# RoverWing-cover-V4.net
KiCad netlist of a schematic drawn in EAGLE
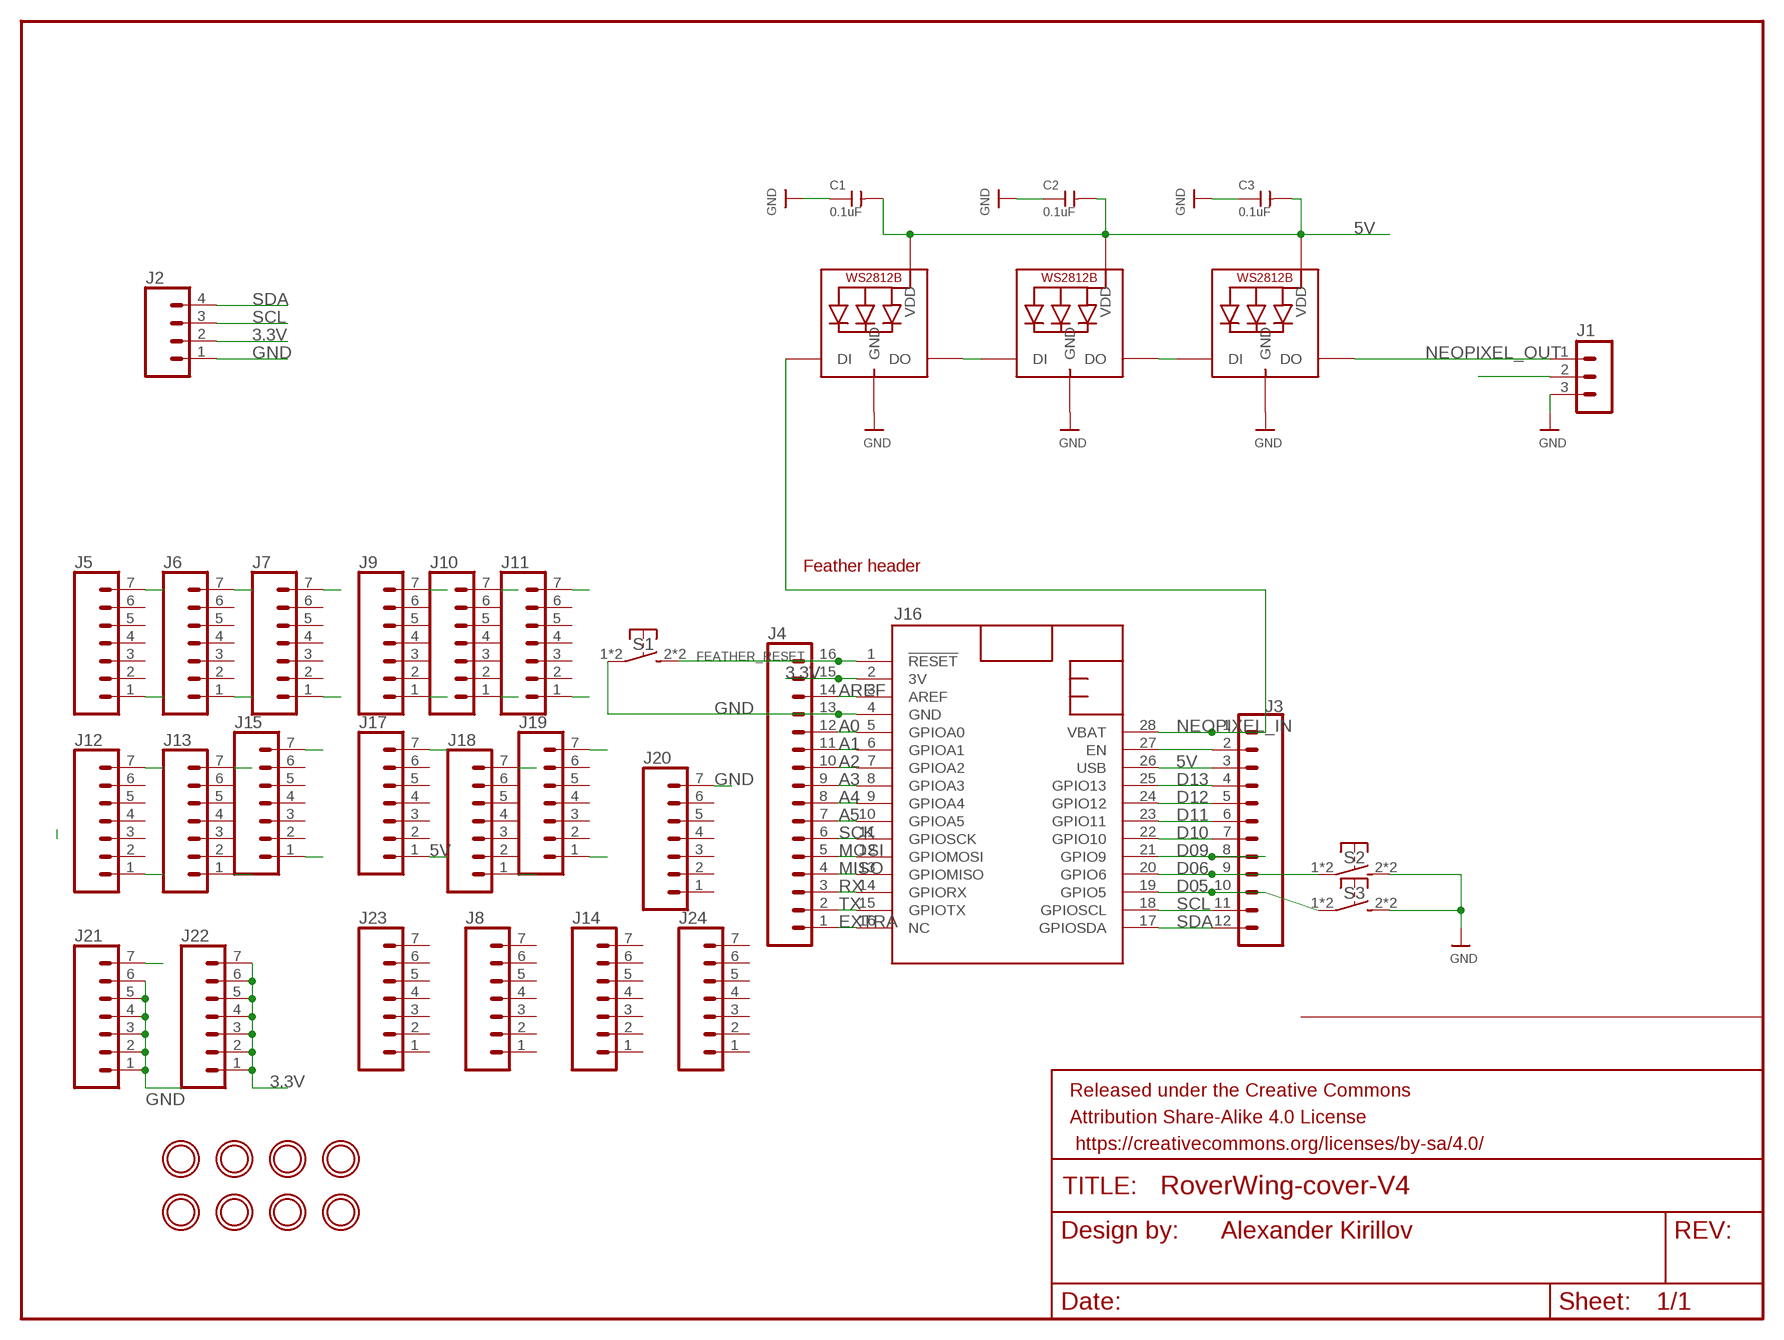
[diagram p0: schematic, sheet 1]

(export (version "E")
  (design (tool "Eeschema 10.0.6"))
  (components
    (comp (ref "C1")
      (value "0.1uF")
      (footprint "eagle-import:C0805")
      (libsource (lib "eagle-import") (part "CAP-CERAMIC-SMD-0805"))
    )
    (comp (ref "C2")
      (value "0.1uF")
      (footprint "eagle-import:C0805")
      (libsource (lib "eagle-import") (part "CAP-CERAMIC-SMD-0805"))
    )
    (comp (ref "C3")
      (value "0.1uF")
      (footprint "eagle-import:C0805")
      (libsource (lib "eagle-import") (part "CAP-CERAMIC-SMD-0805"))
    )
    (comp (ref "FRAME2")
      (value "FRAME-LETTERNO_PACKAGE")
      (footprint "eagle-import:DUMMY")
      (fields (field (name "DESIGNER") "Nobody"))
      (libsource (lib "eagle-import") (part "FRAME-LETTERNO_PACKAGE"))
    )
    (comp (ref "J1")
      (value "HEADER-PH-3P")
      (footprint "eagle-import:B3B-PH-K")
      (fields (field (name "PARTNO") "B3B-PH-K-S(LF)(SN)"))
      (libsource (lib "eagle-import") (part "HEADER-PH-3P"))
    )
    (comp (ref "J2")
      (value "CONN_04")
      (footprint "eagle-import:1X04")
      (libsource (lib "eagle-import") (part "CONN_04"))
    )
    (comp (ref "J3")
      (value "CONN_12NO_SILK")
      (footprint "eagle-import:1X12_NO_SILK")
      (libsource (lib "eagle-import") (part "CONN_12NO_SILK"))
    )
    (comp (ref "J4")
      (value "CONN_161X16_NO_SILK")
      (footprint "eagle-import:1X16_NO_SILK")
      (libsource (lib "eagle-import") (part "CONN_161X16_NO_SILK"))
    )
    (comp (ref "J5")
      (value "CONN_07NO_SILK")
      (footprint "eagle-import:1X07_NO_SILK")
      (libsource (lib "eagle-import") (part "CONN_07NO_SILK"))
    )
    (comp (ref "J6")
      (value "CONN_07NO_SILK")
      (footprint "eagle-import:1X07_NO_SILK")
      (libsource (lib "eagle-import") (part "CONN_07NO_SILK"))
    )
    (comp (ref "J7")
      (value "CONN_07NO_SILK")
      (footprint "eagle-import:1X07_NO_SILK")
      (libsource (lib "eagle-import") (part "CONN_07NO_SILK"))
    )
    (comp (ref "J8")
      (value "CONN_07NO_SILK")
      (footprint "eagle-import:1X07_NO_SILK")
      (libsource (lib "eagle-import") (part "CONN_07NO_SILK"))
    )
    (comp (ref "J9")
      (value "CONN_07NO_SILK")
      (footprint "eagle-import:1X07_NO_SILK")
      (libsource (lib "eagle-import") (part "CONN_07NO_SILK"))
    )
    (comp (ref "J10")
      (value "CONN_07NO_SILK")
      (footprint "eagle-import:1X07_NO_SILK")
      (libsource (lib "eagle-import") (part "CONN_07NO_SILK"))
    )
    (comp (ref "J11")
      (value "CONN_07NO_SILK")
      (footprint "eagle-import:1X07_NO_SILK")
      (libsource (lib "eagle-import") (part "CONN_07NO_SILK"))
    )
    (comp (ref "J12")
      (value "CONN_07NO_SILK")
      (footprint "eagle-import:1X07_NO_SILK")
      (libsource (lib "eagle-import") (part "CONN_07NO_SILK"))
    )
    (comp (ref "J13")
      (value "CONN_07NO_SILK")
      (footprint "eagle-import:1X07_NO_SILK")
      (libsource (lib "eagle-import") (part "CONN_07NO_SILK"))
    )
    (comp (ref "J14")
      (value "CONN_07NO_SILK")
      (footprint "eagle-import:1X07_NO_SILK")
      (libsource (lib "eagle-import") (part "CONN_07NO_SILK"))
    )
    (comp (ref "J15")
      (value "CONN_07NO_SILK")
      (footprint "eagle-import:1X07_NO_SILK")
      (libsource (lib "eagle-import") (part "CONN_07NO_SILK"))
    )
    (comp (ref "J16")
      (value "FEATHERWING_NODIM")
      (footprint "eagle-import:FEATHERWING_DIM")
      (libsource (lib "eagle-import") (part "FEATHERWING_NODIM"))
    )
    (comp (ref "J17")
      (value "CONN_07NO_SILK")
      (footprint "eagle-import:1X07_NO_SILK")
      (libsource (lib "eagle-import") (part "CONN_07NO_SILK"))
    )
    (comp (ref "J18")
      (value "CONN_07NO_SILK")
      (footprint "eagle-import:1X07_NO_SILK")
      (libsource (lib "eagle-import") (part "CONN_07NO_SILK"))
    )
    (comp (ref "J19")
      (value "CONN_07NO_SILK")
      (footprint "eagle-import:1X07_NO_SILK")
      (libsource (lib "eagle-import") (part "CONN_07NO_SILK"))
    )
    (comp (ref "J20")
      (value "CONN_07NO_SILK")
      (footprint "eagle-import:1X07_NO_SILK")
      (libsource (lib "eagle-import") (part "CONN_07NO_SILK"))
    )
    (comp (ref "J21")
      (value "CONN_07NO_SILK")
      (footprint "eagle-import:1X07_NO_SILK")
      (libsource (lib "eagle-import") (part "CONN_07NO_SILK"))
    )
    (comp (ref "J22")
      (value "CONN_07NO_SILK")
      (footprint "eagle-import:1X07_NO_SILK")
      (libsource (lib "eagle-import") (part "CONN_07NO_SILK"))
    )
    (comp (ref "J23")
      (value "CONN_07NO_SILK")
      (footprint "eagle-import:1X07_NO_SILK")
      (libsource (lib "eagle-import") (part "CONN_07NO_SILK"))
    )
    (comp (ref "J24")
      (value "CONN_07NO_SILK")
      (footprint "eagle-import:1X07_NO_SILK")
      (libsource (lib "eagle-import") (part "CONN_07NO_SILK"))
    )
    (comp (ref "LED1")
      (value "WS2812B5050")
      (footprint "eagle-import:WS2812B")
      (libsource (lib "eagle-import") (part "WS2812B5050"))
    )
    (comp (ref "LED2")
      (value "WS2812B5050")
      (footprint "eagle-import:WS2812B")
      (libsource (lib "eagle-import") (part "WS2812B5050"))
    )
    (comp (ref "LED3")
      (value "WS2812B5050")
      (footprint "eagle-import:WS2812B")
      (libsource (lib "eagle-import") (part "WS2812B5050"))
    )
    (comp (ref "S1")
      (value "SW-TACTILE-4.5X4.5_SMD")
      (footprint "eagle-import:TL3305")
      (libsource (lib "eagle-import") (part "SW-TACTILE-4.5X4.5_SMD"))
    )
    (comp (ref "S2")
      (value "SW-TACTILE-4.5X4.5_SMD")
      (footprint "eagle-import:TL3305")
      (libsource (lib "eagle-import") (part "SW-TACTILE-4.5X4.5_SMD"))
    )
    (comp (ref "S3")
      (value "SW-TACTILE-4.5X4.5_SMD")
      (footprint "eagle-import:TL3305")
      (libsource (lib "eagle-import") (part "SW-TACTILE-4.5X4.5_SMD"))
    )
    (comp (ref "U$3")
      (value "MOUNTINGHOLE3.0_NPH")
      (footprint "eagle-import:MOUNTINGHOLE_3.0_NPH")
      (libsource (lib "eagle-import") (part "MOUNTINGHOLE3.0_NPH"))
    )
    (comp (ref "U$4")
      (value "MOUNTINGHOLE3.0_NPH")
      (footprint "eagle-import:MOUNTINGHOLE_3.0_NPH")
      (libsource (lib "eagle-import") (part "MOUNTINGHOLE3.0_NPH"))
    )
    (comp (ref "U$14")
      (value "MOUNTINGHOLE3.0_NPH")
      (footprint "eagle-import:MOUNTINGHOLE_3.0_NPH")
      (libsource (lib "eagle-import") (part "MOUNTINGHOLE3.0_NPH"))
    )
    (comp (ref "U$15")
      (value "MOUNTINGHOLE3.0_NPH")
      (footprint "eagle-import:MOUNTINGHOLE_3.0_NPH")
      (libsource (lib "eagle-import") (part "MOUNTINGHOLE3.0_NPH"))
    )
    (comp (ref "U$24")
      (value "MOUNTINGHOLE3.0_NPH")
      (footprint "eagle-import:MOUNTINGHOLE_3.0_NPH")
      (libsource (lib "eagle-import") (part "MOUNTINGHOLE3.0_NPH"))
    )
    (comp (ref "U$25")
      (value "MOUNTINGHOLE3.0_NPH")
      (footprint "eagle-import:MOUNTINGHOLE_3.0_NPH")
      (libsource (lib "eagle-import") (part "MOUNTINGHOLE3.0_NPH"))
    )
    (comp (ref "U$26")
      (value "MOUNTINGHOLE3.0_NPH")
      (footprint "eagle-import:MOUNTINGHOLE_3.0_NPH")
      (libsource (lib "eagle-import") (part "MOUNTINGHOLE3.0_NPH"))
    )
    (comp (ref "U$27")
      (value "MOUNTINGHOLE3.0_NPH")
      (footprint "eagle-import:MOUNTINGHOLE_3.0_NPH")
      (libsource (lib "eagle-import") (part "MOUNTINGHOLE3.0_NPH"))
    )
  )
  (nets
    (net (code "1") (name "/3.3V") (class "Default")
      (node (ref "J16") (pin "2") (pinfunction "3V_2") (pintype "power_in"))
      (node (ref "J2") (pin "2") (pinfunction "2_2") (pintype "passive"))
      (node (ref "J22") (pin "1") (pinfunction "1_1") (pintype "passive"))
      (node (ref "J22") (pin "2") (pinfunction "2_2") (pintype "passive"))
      (node (ref "J22") (pin "3") (pinfunction "3_3") (pintype "passive"))
      (node (ref "J22") (pin "4") (pinfunction "4_4") (pintype "passive"))
      (node (ref "J22") (pin "5") (pinfunction "5_5") (pintype "passive"))
      (node (ref "J22") (pin "6") (pinfunction "6_6") (pintype "passive"))
      (node (ref "J22") (pin "7") (pinfunction "7_7") (pintype "passive"))
      (node (ref "J4") (pin "15") (pinfunction "15_15") (pintype "passive"))
    )
    (net (code "2") (name "/5V") (class "Default")
      (node (ref "C1") (pin "2") (pinfunction "2_2") (pintype "passive"))
      (node (ref "C2") (pin "2") (pinfunction "2_2") (pintype "passive"))
      (node (ref "C3") (pin "2") (pinfunction "2_2") (pintype "passive"))
      (node (ref "J1") (pin "2") (pinfunction "2_2") (pintype "passive"))
      (node (ref "J16") (pin "26") (pinfunction "USB_26") (pintype "power_in"))
      (node (ref "J17") (pin "1") (pinfunction "1_1") (pintype "passive"))
      (node (ref "J3") (pin "3") (pinfunction "3_3") (pintype "passive"))
      (node (ref "LED1") (pin "1-VDD") (pinfunction "VDD_1-VDD") (pintype "power_in"))
      (node (ref "LED2") (pin "1-VDD") (pinfunction "VDD_1-VDD") (pintype "power_in"))
      (node (ref "LED3") (pin "1-VDD") (pinfunction "VDD_1-VDD") (pintype "power_in"))
    )
    (net (code "3") (name "/A0") (class "Default")
      (node (ref "J16") (pin "5") (pinfunction "GPIOA0_5") (pintype "bidirectional"))
      (node (ref "J19") (pin "7") (pinfunction "7_7") (pintype "passive"))
      (node (ref "J4") (pin "12") (pinfunction "12_12") (pintype "passive"))
    )
    (net (code "4") (name "/A1") (class "Default")
      (node (ref "J16") (pin "6") (pinfunction "GPIOA1_6") (pintype "bidirectional"))
      (node (ref "J18") (pin "7") (pinfunction "7_7") (pintype "passive"))
      (node (ref "J4") (pin "11") (pinfunction "11_11") (pintype "passive"))
    )
    (net (code "5") (name "/A2") (class "Default")
      (node (ref "J16") (pin "7") (pinfunction "GPIOA2_7") (pintype "bidirectional"))
      (node (ref "J17") (pin "7") (pinfunction "7_7") (pintype "passive"))
      (node (ref "J4") (pin "10") (pinfunction "10_10") (pintype "passive"))
    )
    (net (code "6") (name "/A3") (class "Default")
      (node (ref "J15") (pin "7") (pinfunction "7_7") (pintype "passive"))
      (node (ref "J16") (pin "8") (pinfunction "GPIOA3_8") (pintype "bidirectional"))
      (node (ref "J4") (pin "9") (pinfunction "9_9") (pintype "passive"))
    )
    (net (code "7") (name "/A4") (class "Default")
      (node (ref "J13") (pin "7") (pinfunction "7_7") (pintype "passive"))
      (node (ref "J16") (pin "9") (pinfunction "GPIOA4_9") (pintype "bidirectional"))
      (node (ref "J4") (pin "8") (pinfunction "8_8") (pintype "passive"))
    )
    (net (code "8") (name "/A5") (class "Default")
      (node (ref "J12") (pin "7") (pinfunction "7_7") (pintype "passive"))
      (node (ref "J16") (pin "10") (pinfunction "GPIOA5_10") (pintype "bidirectional"))
      (node (ref "J4") (pin "7") (pinfunction "7_7") (pintype "passive"))
    )
    (net (code "9") (name "/AREF") (class "Default")
      (node (ref "J16") (pin "3") (pinfunction "AREF_3") (pintype "passive"))
      (node (ref "J21") (pin "7") (pinfunction "7_7") (pintype "passive"))
      (node (ref "J4") (pin "14") (pinfunction "14_14") (pintype "passive"))
    )
    (net (code "10") (name "/D05") (class "Default")
      (node (ref "J16") (pin "19") (pinfunction "GPIO5_19") (pintype "bidirectional"))
      (node (ref "J3") (pin "10") (pinfunction "10_10") (pintype "passive"))
      (node (ref "J7") (pin "1") (pinfunction "1_1") (pintype "passive"))
      (node (ref "S3") (pin "1") (pinfunction "P1_1") (pintype "passive"))
      (node (ref "S3") (pin "4") (pinfunction "P1_4") (pintype "passive"))
    )
    (net (code "11") (name "/D06") (class "Default")
      (node (ref "J16") (pin "20") (pinfunction "GPIO6_20") (pintype "bidirectional"))
      (node (ref "J3") (pin "9") (pinfunction "9_9") (pintype "passive"))
      (node (ref "J9") (pin "1") (pinfunction "1_1") (pintype "passive"))
      (node (ref "S2") (pin "1") (pinfunction "P1_1") (pintype "passive"))
      (node (ref "S2") (pin "4") (pinfunction "P1_4") (pintype "passive"))
    )
    (net (code "12") (name "/D09") (class "Default")
      (node (ref "J10") (pin "1") (pinfunction "1_1") (pintype "passive"))
      (node (ref "J16") (pin "21") (pinfunction "GPIO9_21") (pintype "bidirectional"))
      (node (ref "J3") (pin "8") (pinfunction "8_8") (pintype "passive"))
    )
    (net (code "13") (name "/D10") (class "Default")
      (node (ref "J11") (pin "1") (pinfunction "1_1") (pintype "passive"))
      (node (ref "J16") (pin "22") (pinfunction "GPIO10_22") (pintype "bidirectional"))
      (node (ref "J3") (pin "7") (pinfunction "7_7") (pintype "passive"))
    )
    (net (code "14") (name "/D11") (class "Default")
      (node (ref "J12") (pin "1") (pinfunction "1_1") (pintype "passive"))
      (node (ref "J16") (pin "23") (pinfunction "GPIO11_23") (pintype "bidirectional"))
      (node (ref "J3") (pin "6") (pinfunction "6_6") (pintype "passive"))
    )
    (net (code "15") (name "/D12") (class "Default")
      (node (ref "J13") (pin "1") (pinfunction "1_1") (pintype "passive"))
      (node (ref "J16") (pin "24") (pinfunction "GPIO12_24") (pintype "bidirectional"))
      (node (ref "J3") (pin "5") (pinfunction "5_5") (pintype "passive"))
    )
    (net (code "16") (name "/D13") (class "Default")
      (node (ref "J15") (pin "1") (pinfunction "1_1") (pintype "passive"))
      (node (ref "J16") (pin "25") (pinfunction "GPIO13_25") (pintype "bidirectional"))
      (node (ref "J3") (pin "4") (pinfunction "4_4") (pintype "passive"))
    )
    (net (code "17") (name "/EXTRA") (class "Default")
      (node (ref "J16") (pin "16") (pinfunction "NC_16") (pintype "passive"))
      (node (ref "J4") (pin "1") (pinfunction "1_1") (pintype "passive"))
      (node (ref "J5") (pin "7") (pinfunction "7_7") (pintype "passive"))
    )
    (net (code "18") (name "/FEATHER_RESET") (class "Default")
      (node (ref "J16") (pin "1") (pinfunction "~{RESET}_1") (pintype "input"))
      (node (ref "J4") (pin "16") (pinfunction "16_16") (pintype "passive"))
      (node (ref "S1") (pin "2") (pinfunction "S1_2") (pintype "passive"))
      (node (ref "S1") (pin "3") (pinfunction "S1_3") (pintype "passive"))
    )
    (net (code "19") (name "/MISO") (class "Default")
      (node (ref "J16") (pin "13") (pinfunction "GPIOMISO_13") (pintype "bidirectional"))
      (node (ref "J4") (pin "4") (pinfunction "4_4") (pintype "passive"))
      (node (ref "J9") (pin "7") (pinfunction "7_7") (pintype "passive"))
    )
    (net (code "20") (name "/MOSI") (class "Default")
      (node (ref "J10") (pin "7") (pinfunction "7_7") (pintype "passive"))
      (node (ref "J16") (pin "12") (pinfunction "GPIOMOSI_12") (pintype "bidirectional"))
      (node (ref "J4") (pin "5") (pinfunction "5_5") (pintype "passive"))
    )
    (net (code "21") (name "/N$37") (class "Default")
      (node (ref "J16") (pin "27") (pinfunction "EN_27") (pintype "passive"))
      (node (ref "J18") (pin "1") (pinfunction "1_1") (pintype "passive"))
      (node (ref "J3") (pin "2") (pinfunction "2_2") (pintype "passive"))
    )
    (net (code "22") (name "/NEOPIXEL_IN") (class "Default")
      (node (ref "J16") (pin "28") (pinfunction "VBAT_28") (pintype "power_in"))
      (node (ref "J3") (pin "1") (pinfunction "1_1") (pintype "passive"))
      (node (ref "LED1") (pin "4-DIN") (pinfunction "DI_4-DIN") (pintype "input"))
    )
    (net (code "23") (name "/NEOPIXEL_OUT") (class "Default")
      (node (ref "J1") (pin "1") (pinfunction "1_1") (pintype "passive"))
      (node (ref "LED3") (pin "2-DOUT") (pinfunction "DO_2-DOUT") (pintype "output"))
    )
    (net (code "24") (name "/RX") (class "Default")
      (node (ref "J16") (pin "14") (pinfunction "GPIORX_14") (pintype "bidirectional"))
      (node (ref "J4") (pin "3") (pinfunction "3_3") (pintype "passive"))
      (node (ref "J7") (pin "7") (pinfunction "7_7") (pintype "passive"))
    )
    (net (code "25") (name "/SCK") (class "Default")
      (node (ref "J11") (pin "7") (pinfunction "7_7") (pintype "passive"))
      (node (ref "J16") (pin "11") (pinfunction "GPIOSCK_11") (pintype "bidirectional"))
      (node (ref "J4") (pin "6") (pinfunction "6_6") (pintype "passive"))
    )
    (net (code "26") (name "/SCL") (class "Default")
      (node (ref "J16") (pin "18") (pinfunction "GPIOSCL_18") (pintype "bidirectional"))
      (node (ref "J2") (pin "3") (pinfunction "3_3") (pintype "passive"))
      (node (ref "J3") (pin "11") (pinfunction "11_11") (pintype "passive"))
      (node (ref "J6") (pin "1") (pinfunction "1_1") (pintype "passive"))
    )
    (net (code "27") (name "/SDA") (class "Default")
      (node (ref "J16") (pin "17") (pinfunction "GPIOSDA_17") (pintype "bidirectional"))
      (node (ref "J2") (pin "4") (pinfunction "4_4") (pintype "passive"))
      (node (ref "J3") (pin "12") (pinfunction "12_12") (pintype "passive"))
      (node (ref "J5") (pin "1") (pinfunction "1_1") (pintype "passive"))
    )
    (net (code "28") (name "/TX") (class "Default")
      (node (ref "J16") (pin "15") (pinfunction "GPIOTX_15") (pintype "bidirectional"))
      (node (ref "J4") (pin "2") (pinfunction "2_2") (pintype "passive"))
      (node (ref "J6") (pin "7") (pinfunction "7_7") (pintype "passive"))
    )
    (net (code "29") (name "GND") (class "Default")
      (node (ref "C1") (pin "1") (pinfunction "1_1") (pintype "passive"))
      (node (ref "C2") (pin "1") (pinfunction "1_1") (pintype "passive"))
      (node (ref "C3") (pin "1") (pinfunction "1_1") (pintype "passive"))
      (node (ref "J1") (pin "3") (pinfunction "3_3") (pintype "passive"))
      (node (ref "J16") (pin "4") (pinfunction "GND_4") (pintype "power_in"))
      (node (ref "J2") (pin "1") (pinfunction "1_1") (pintype "passive"))
      (node (ref "J20") (pin "7") (pinfunction "7_7") (pintype "passive"))
      (node (ref "J21") (pin "1") (pinfunction "1_1") (pintype "passive"))
      (node (ref "J21") (pin "2") (pinfunction "2_2") (pintype "passive"))
      (node (ref "J21") (pin "3") (pinfunction "3_3") (pintype "passive"))
      (node (ref "J21") (pin "4") (pinfunction "4_4") (pintype "passive"))
      (node (ref "J21") (pin "5") (pinfunction "5_5") (pintype "passive"))
      (node (ref "J21") (pin "6") (pinfunction "6_6") (pintype "passive"))
      (node (ref "J4") (pin "13") (pinfunction "13_13") (pintype "passive"))
      (node (ref "LED1") (pin "3-GND") (pinfunction "GND_3-GND") (pintype "power_in"))
      (node (ref "LED2") (pin "3-GND") (pinfunction "GND_3-GND") (pintype "power_in"))
      (node (ref "LED3") (pin "3-GND") (pinfunction "GND_3-GND") (pintype "power_in"))
      (node (ref "S1") (pin "1") (pinfunction "P1_1") (pintype "passive"))
      (node (ref "S1") (pin "4") (pinfunction "P1_4") (pintype "passive"))
      (node (ref "S2") (pin "2") (pinfunction "S1_2") (pintype "passive"))
      (node (ref "S2") (pin "3") (pinfunction "S1_3") (pintype "passive"))
      (node (ref "S3") (pin "2") (pinfunction "S1_2") (pintype "passive"))
      (node (ref "S3") (pin "3") (pinfunction "S1_3") (pintype "passive"))
    )
    (net (code "30") (name "Net-(LED1-DO)") (class "Default")
      (node (ref "LED1") (pin "2-DOUT") (pinfunction "DO_2-DOUT") (pintype "output"))
      (node (ref "LED2") (pin "4-DIN") (pinfunction "DI_4-DIN") (pintype "input"))
    )
    (net (code "31") (name "Net-(LED2-DO)") (class "Default")
      (node (ref "LED2") (pin "2-DOUT") (pinfunction "DO_2-DOUT") (pintype "output"))
      (node (ref "LED3") (pin "4-DIN") (pinfunction "DI_4-DIN") (pintype "input"))
    )
    (net (code "32") (name "unconnected-(J5-Pad2)") (class "Default")
      (node (ref "J5") (pin "2") (pinfunction "2_2") (pintype "passive"))
    )
    (net (code "33") (name "unconnected-(J5-Pad3)") (class "Default")
      (node (ref "J5") (pin "3") (pinfunction "3_3") (pintype "passive"))
    )
    (net (code "34") (name "unconnected-(J5-Pad4)") (class "Default")
      (node (ref "J5") (pin "4") (pinfunction "4_4") (pintype "passive"))
    )
    (net (code "35") (name "unconnected-(J5-Pad5)") (class "Default")
      (node (ref "J5") (pin "5") (pinfunction "5_5") (pintype "passive"))
    )
    (net (code "36") (name "unconnected-(J5-Pad6)") (class "Default")
      (node (ref "J5") (pin "6") (pinfunction "6_6") (pintype "passive"))
    )
    (net (code "37") (name "unconnected-(J6-Pad2)") (class "Default")
      (node (ref "J6") (pin "2") (pinfunction "2_2") (pintype "passive"))
    )
    (net (code "38") (name "unconnected-(J6-Pad3)") (class "Default")
      (node (ref "J6") (pin "3") (pinfunction "3_3") (pintype "passive"))
    )
    (net (code "39") (name "unconnected-(J6-Pad4)") (class "Default")
      (node (ref "J6") (pin "4") (pinfunction "4_4") (pintype "passive"))
    )
    (net (code "40") (name "unconnected-(J6-Pad5)") (class "Default")
      (node (ref "J6") (pin "5") (pinfunction "5_5") (pintype "passive"))
    )
    (net (code "41") (name "unconnected-(J6-Pad6)") (class "Default")
      (node (ref "J6") (pin "6") (pinfunction "6_6") (pintype "passive"))
    )
    (net (code "42") (name "unconnected-(J7-Pad2)") (class "Default")
      (node (ref "J7") (pin "2") (pinfunction "2_2") (pintype "passive"))
    )
    (net (code "43") (name "unconnected-(J7-Pad3)") (class "Default")
      (node (ref "J7") (pin "3") (pinfunction "3_3") (pintype "passive"))
    )
    (net (code "44") (name "unconnected-(J7-Pad4)") (class "Default")
      (node (ref "J7") (pin "4") (pinfunction "4_4") (pintype "passive"))
    )
    (net (code "45") (name "unconnected-(J7-Pad5)") (class "Default")
      (node (ref "J7") (pin "5") (pinfunction "5_5") (pintype "passive"))
    )
    (net (code "46") (name "unconnected-(J7-Pad6)") (class "Default")
      (node (ref "J7") (pin "6") (pinfunction "6_6") (pintype "passive"))
    )
    (net (code "47") (name "unconnected-(J8-Pad1)") (class "Default")
      (node (ref "J8") (pin "1") (pinfunction "1_1") (pintype "passive"))
    )
    (net (code "48") (name "unconnected-(J8-Pad2)") (class "Default")
      (node (ref "J8") (pin "2") (pinfunction "2_2") (pintype "passive"))
    )
    (net (code "49") (name "unconnected-(J8-Pad3)") (class "Default")
      (node (ref "J8") (pin "3") (pinfunction "3_3") (pintype "passive"))
    )
    (net (code "50") (name "unconnected-(J8-Pad4)") (class "Default")
      (node (ref "J8") (pin "4") (pinfunction "4_4") (pintype "passive"))
    )
    (net (code "51") (name "unconnected-(J8-Pad5)") (class "Default")
      (node (ref "J8") (pin "5") (pinfunction "5_5") (pintype "passive"))
    )
    (net (code "52") (name "unconnected-(J8-Pad6)") (class "Default")
      (node (ref "J8") (pin "6") (pinfunction "6_6") (pintype "passive"))
    )
    (net (code "53") (name "unconnected-(J8-Pad7)") (class "Default")
      (node (ref "J8") (pin "7") (pinfunction "7_7") (pintype "passive"))
    )
    (net (code "54") (name "unconnected-(J9-Pad2)") (class "Default")
      (node (ref "J9") (pin "2") (pinfunction "2_2") (pintype "passive"))
    )
    (net (code "55") (name "unconnected-(J9-Pad3)") (class "Default")
      (node (ref "J9") (pin "3") (pinfunction "3_3") (pintype "passive"))
    )
    (net (code "56") (name "unconnected-(J9-Pad4)") (class "Default")
      (node (ref "J9") (pin "4") (pinfunction "4_4") (pintype "passive"))
    )
    (net (code "57") (name "unconnected-(J9-Pad5)") (class "Default")
      (node (ref "J9") (pin "5") (pinfunction "5_5") (pintype "passive"))
    )
    (net (code "58") (name "unconnected-(J9-Pad6)") (class "Default")
      (node (ref "J9") (pin "6") (pinfunction "6_6") (pintype "passive"))
    )
    (net (code "59") (name "unconnected-(J10-Pad2)") (class "Default")
      (node (ref "J10") (pin "2") (pinfunction "2_2") (pintype "passive"))
    )
    (net (code "60") (name "unconnected-(J10-Pad3)") (class "Default")
      (node (ref "J10") (pin "3") (pinfunction "3_3") (pintype "passive"))
    )
    (net (code "61") (name "unconnected-(J10-Pad4)") (class "Default")
      (node (ref "J10") (pin "4") (pinfunction "4_4") (pintype "passive"))
    )
    (net (code "62") (name "unconnected-(J10-Pad5)") (class "Default")
      (node (ref "J10") (pin "5") (pinfunction "5_5") (pintype "passive"))
    )
    (net (code "63") (name "unconnected-(J10-Pad6)") (class "Default")
      (node (ref "J10") (pin "6") (pinfunction "6_6") (pintype "passive"))
    )
    (net (code "64") (name "unconnected-(J11-Pad2)") (class "Default")
      (node (ref "J11") (pin "2") (pinfunction "2_2") (pintype "passive"))
    )
    (net (code "65") (name "unconnected-(J11-Pad3)") (class "Default")
      (node (ref "J11") (pin "3") (pinfunction "3_3") (pintype "passive"))
    )
    (net (code "66") (name "unconnected-(J11-Pad4)") (class "Default")
      (node (ref "J11") (pin "4") (pinfunction "4_4") (pintype "passive"))
    )
    (net (code "67") (name "unconnected-(J11-Pad5)") (class "Default")
      (node (ref "J11") (pin "5") (pinfunction "5_5") (pintype "passive"))
    )
    (net (code "68") (name "unconnected-(J11-Pad6)") (class "Default")
      (node (ref "J11") (pin "6") (pinfunction "6_6") (pintype "passive"))
    )
    (net (code "69") (name "unconnected-(J12-Pad2)") (class "Default")
      (node (ref "J12") (pin "2") (pinfunction "2_2") (pintype "passive"))
    )
    (net (code "70") (name "unconnected-(J12-Pad3)") (class "Default")
      (node (ref "J12") (pin "3") (pinfunction "3_3") (pintype "passive"))
    )
    (net (code "71") (name "unconnected-(J12-Pad4)") (class "Default")
      (node (ref "J12") (pin "4") (pinfunction "4_4") (pintype "passive"))
    )
    (net (code "72") (name "unconnected-(J12-Pad5)") (class "Default")
      (node (ref "J12") (pin "5") (pinfunction "5_5") (pintype "passive"))
    )
    (net (code "73") (name "unconnected-(J12-Pad6)") (class "Default")
      (node (ref "J12") (pin "6") (pinfunction "6_6") (pintype "passive"))
    )
    (net (code "74") (name "unconnected-(J13-Pad2)") (class "Default")
      (node (ref "J13") (pin "2") (pinfunction "2_2") (pintype "passive"))
    )
    (net (code "75") (name "unconnected-(J13-Pad3)") (class "Default")
      (node (ref "J13") (pin "3") (pinfunction "3_3") (pintype "passive"))
    )
    (net (code "76") (name "unconnected-(J13-Pad4)") (class "Default")
      (node (ref "J13") (pin "4") (pinfunction "4_4") (pintype "passive"))
    )
    (net (code "77") (name "unconnected-(J13-Pad5)") (class "Default")
      (node (ref "J13") (pin "5") (pinfunction "5_5") (pintype "passive"))
    )
    (net (code "78") (name "unconnected-(J13-Pad6)") (class "Default")
      (node (ref "J13") (pin "6") (pinfunction "6_6") (pintype "passive"))
    )
    (net (code "79") (name "unconnected-(J14-Pad1)") (class "Default")
      (node (ref "J14") (pin "1") (pinfunction "1_1") (pintype "passive"))
    )
    (net (code "80") (name "unconnected-(J14-Pad2)") (class "Default")
      (node (ref "J14") (pin "2") (pinfunction "2_2") (pintype "passive"))
    )
    (net (code "81") (name "unconnected-(J14-Pad3)") (class "Default")
      (node (ref "J14") (pin "3") (pinfunction "3_3") (pintype "passive"))
    )
    (net (code "82") (name "unconnected-(J14-Pad4)") (class "Default")
      (node (ref "J14") (pin "4") (pinfunction "4_4") (pintype "passive"))
    )
    (net (code "83") (name "unconnected-(J14-Pad5)") (class "Default")
      (node (ref "J14") (pin "5") (pinfunction "5_5") (pintype "passive"))
    )
    (net (code "84") (name "unconnected-(J14-Pad6)") (class "Default")
      (node (ref "J14") (pin "6") (pinfunction "6_6") (pintype "passive"))
    )
    (net (code "85") (name "unconnected-(J14-Pad7)") (class "Default")
      (node (ref "J14") (pin "7") (pinfunction "7_7") (pintype "passive"))
    )
    (net (code "86") (name "unconnected-(J15-Pad2)") (class "Default")
      (node (ref "J15") (pin "2") (pinfunction "2_2") (pintype "passive"))
    )
    (net (code "87") (name "unconnected-(J15-Pad3)") (class "Default")
      (node (ref "J15") (pin "3") (pinfunction "3_3") (pintype "passive"))
    )
    (net (code "88") (name "unconnected-(J15-Pad4)") (class "Default")
      (node (ref "J15") (pin "4") (pinfunction "4_4") (pintype "passive"))
    )
    (net (code "89") (name "unconnected-(J15-Pad5)") (class "Default")
      (node (ref "J15") (pin "5") (pinfunction "5_5") (pintype "passive"))
    )
    (net (code "90") (name "unconnected-(J15-Pad6)") (class "Default")
      (node (ref "J15") (pin "6") (pinfunction "6_6") (pintype "passive"))
    )
    (net (code "91") (name "unconnected-(J17-Pad2)") (class "Default")
      (node (ref "J17") (pin "2") (pinfunction "2_2") (pintype "passive"))
    )
    (net (code "92") (name "unconnected-(J17-Pad3)") (class "Default")
      (node (ref "J17") (pin "3") (pinfunction "3_3") (pintype "passive"))
    )
    (net (code "93") (name "unconnected-(J17-Pad4)") (class "Default")
      (node (ref "J17") (pin "4") (pinfunction "4_4") (pintype "passive"))
    )
    (net (code "94") (name "unconnected-(J17-Pad5)") (class "Default")
      (node (ref "J17") (pin "5") (pinfunction "5_5") (pintype "passive"))
    )
    (net (code "95") (name "unconnected-(J17-Pad6)") (class "Default")
      (node (ref "J17") (pin "6") (pinfunction "6_6") (pintype "passive"))
    )
    (net (code "96") (name "unconnected-(J18-Pad2)") (class "Default")
      (node (ref "J18") (pin "2") (pinfunction "2_2") (pintype "passive"))
    )
    (net (code "97") (name "unconnected-(J18-Pad3)") (class "Default")
      (node (ref "J18") (pin "3") (pinfunction "3_3") (pintype "passive"))
    )
    (net (code "98") (name "unconnected-(J18-Pad4)") (class "Default")
      (node (ref "J18") (pin "4") (pinfunction "4_4") (pintype "passive"))
    )
    (net (code "99") (name "unconnected-(J18-Pad5)") (class "Default")
      (node (ref "J18") (pin "5") (pinfunction "5_5") (pintype "passive"))
    )
    (net (code "100") (name "unconnected-(J18-Pad6)") (class "Default")
      (node (ref "J18") (pin "6") (pinfunction "6_6") (pintype "passive"))
    )
    (net (code "101") (name "unconnected-(J19-Pad1)") (class "Default")
      (node (ref "J19") (pin "1") (pinfunction "1_1") (pintype "passive"))
    )
    (net (code "102") (name "unconnected-(J19-Pad2)") (class "Default")
      (node (ref "J19") (pin "2") (pinfunction "2_2") (pintype "passive"))
    )
    (net (code "103") (name "unconnected-(J19-Pad3)") (class "Default")
      (node (ref "J19") (pin "3") (pinfunction "3_3") (pintype "passive"))
    )
    (net (code "104") (name "unconnected-(J19-Pad4)") (class "Default")
      (node (ref "J19") (pin "4") (pinfunction "4_4") (pintype "passive"))
    )
    (net (code "105") (name "unconnected-(J19-Pad5)") (class "Default")
      (node (ref "J19") (pin "5") (pinfunction "5_5") (pintype "passive"))
    )
    (net (code "106") (name "unconnected-(J19-Pad6)") (class "Default")
      (node (ref "J19") (pin "6") (pinfunction "6_6") (pintype "passive"))
    )
    (net (code "107") (name "unconnected-(J20-Pad1)") (class "Default")
      (node (ref "J20") (pin "1") (pinfunction "1_1") (pintype "passive"))
    )
    (net (code "108") (name "unconnected-(J20-Pad2)") (class "Default")
      (node (ref "J20") (pin "2") (pinfunction "2_2") (pintype "passive"))
    )
    (net (code "109") (name "unconnected-(J20-Pad3)") (class "Default")
      (node (ref "J20") (pin "3") (pinfunction "3_3") (pintype "passive"))
    )
    (net (code "110") (name "unconnected-(J20-Pad4)") (class "Default")
      (node (ref "J20") (pin "4") (pinfunction "4_4") (pintype "passive"))
    )
    (net (code "111") (name "unconnected-(J20-Pad5)") (class "Default")
      (node (ref "J20") (pin "5") (pinfunction "5_5") (pintype "passive"))
    )
    (net (code "112") (name "unconnected-(J20-Pad6)") (class "Default")
      (node (ref "J20") (pin "6") (pinfunction "6_6") (pintype "passive"))
    )
    (net (code "113") (name "unconnected-(J23-Pad1)") (class "Default")
      (node (ref "J23") (pin "1") (pinfunction "1_1") (pintype "passive"))
    )
    (net (code "114") (name "unconnected-(J23-Pad2)") (class "Default")
      (node (ref "J23") (pin "2") (pinfunction "2_2") (pintype "passive"))
    )
    (net (code "115") (name "unconnected-(J23-Pad3)") (class "Default")
      (node (ref "J23") (pin "3") (pinfunction "3_3") (pintype "passive"))
    )
    (net (code "116") (name "unconnected-(J23-Pad4)") (class "Default")
      (node (ref "J23") (pin "4") (pinfunction "4_4") (pintype "passive"))
    )
    (net (code "117") (name "unconnected-(J23-Pad5)") (class "Default")
      (node (ref "J23") (pin "5") (pinfunction "5_5") (pintype "passive"))
    )
    (net (code "118") (name "unconnected-(J23-Pad6)") (class "Default")
      (node (ref "J23") (pin "6") (pinfunction "6_6") (pintype "passive"))
    )
    (net (code "119") (name "unconnected-(J23-Pad7)") (class "Default")
      (node (ref "J23") (pin "7") (pinfunction "7_7") (pintype "passive"))
    )
    (net (code "120") (name "unconnected-(J24-Pad1)") (class "Default")
      (node (ref "J24") (pin "1") (pinfunction "1_1") (pintype "passive"))
    )
    (net (code "121") (name "unconnected-(J24-Pad2)") (class "Default")
      (node (ref "J24") (pin "2") (pinfunction "2_2") (pintype "passive"))
    )
    (net (code "122") (name "unconnected-(J24-Pad3)") (class "Default")
      (node (ref "J24") (pin "3") (pinfunction "3_3") (pintype "passive"))
    )
    (net (code "123") (name "unconnected-(J24-Pad4)") (class "Default")
      (node (ref "J24") (pin "4") (pinfunction "4_4") (pintype "passive"))
    )
    (net (code "124") (name "unconnected-(J24-Pad5)") (class "Default")
      (node (ref "J24") (pin "5") (pinfunction "5_5") (pintype "passive"))
    )
    (net (code "125") (name "unconnected-(J24-Pad6)") (class "Default")
      (node (ref "J24") (pin "6") (pinfunction "6_6") (pintype "passive"))
    )
    (net (code "126") (name "unconnected-(J24-Pad7)") (class "Default")
      (node (ref "J24") (pin "7") (pinfunction "7_7") (pintype "passive"))
    )
  )
)
